# protoBoardHB.net
KiCad netlist of a schematic drawn in EAGLE
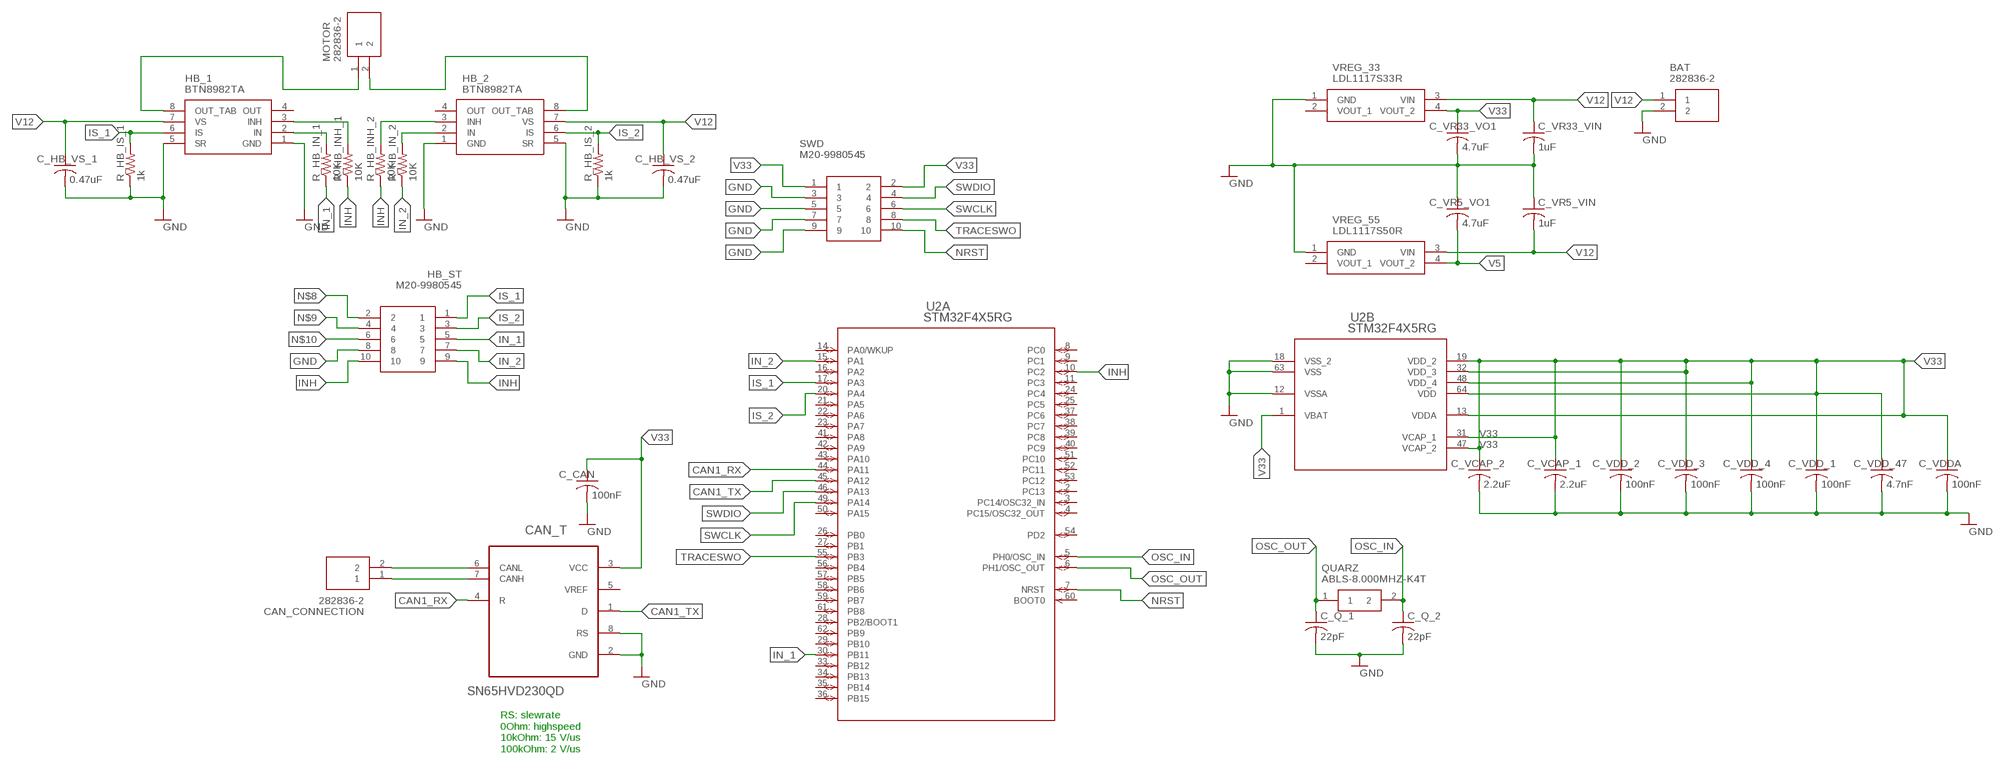
[diagram p0: schematic, sheet 1]

(export (version "E")
  (design (tool "Eeschema 10.0.6"))
  (components
    (comp (ref "BAT")
      (value "282836-2")
      (footprint "eagle-import:SHDR2W100P0X500_1X2_1000X820X1")
      (fields (field (name "MOUSER_PART_NUMBER") "571-2828362"))
      (libsource (lib "eagle-import") (part "282836-2"))
    )
    (comp (ref "CAN_CONNECTION")
      (value "282836-2")
      (footprint "eagle-import:SHDR2W100P0X500_1X2_1000X820X1")
      (fields (field (name "MOUSER_PART_NUMBER") "571-2828362"))
      (libsource (lib "eagle-import") (part "282836-2"))
    )
    (comp (ref "CAN_T")
      (value "SN65HVD230QD")
      (footprint "eagle-import:SOIC127P600X175-8N")
      (fields (field (name "MF") "TEXAS INSTRUMENTS") (field (name "MPN") "SN65HVD230QD.."))
      (libsource (lib "eagle-import") (part "SN65HVD230QD"))
    )
    (comp (ref "C_CAN")
      (value "100nF")
      (footprint "eagle-import:C1206")
      (libsource (lib "eagle-import") (part "C-USC1206"))
    )
    (comp (ref "C_HB_VS_1")
      (value "0.47uF")
      (footprint "eagle-import:C1206")
      (libsource (lib "eagle-import") (part "C-USC1206"))
    )
    (comp (ref "C_HB_VS_2")
      (value "0.47uF")
      (footprint "eagle-import:C1206")
      (libsource (lib "eagle-import") (part "C-USC1206"))
    )
    (comp (ref "C_Q_1")
      (value "22pF")
      (footprint "eagle-import:C0805")
      (libsource (lib "eagle-import") (part "C-USC0805"))
    )
    (comp (ref "C_Q_2")
      (value "22pF")
      (footprint "eagle-import:C0805")
      (libsource (lib "eagle-import") (part "C-USC0805"))
    )
    (comp (ref "C_VCAP_1")
      (value "2.2uF")
      (footprint "eagle-import:C1206")
      (libsource (lib "eagle-import") (part "C-USC1206"))
    )
    (comp (ref "C_VCAP_2")
      (value "2.2uF")
      (footprint "eagle-import:C1206")
      (libsource (lib "eagle-import") (part "C-USC1206"))
    )
    (comp (ref "C_VDDA")
      (value "100nF")
      (footprint "eagle-import:C1206")
      (libsource (lib "eagle-import") (part "C-USC1206"))
    )
    (comp (ref "C_VDD_1")
      (value "100nF")
      (footprint "eagle-import:C1206")
      (libsource (lib "eagle-import") (part "C-USC1206"))
    )
    (comp (ref "C_VDD_2")
      (value "100nF")
      (footprint "eagle-import:C1206")
      (libsource (lib "eagle-import") (part "C-USC1206"))
    )
    (comp (ref "C_VDD_3")
      (value "100nF")
      (footprint "eagle-import:C1206")
      (libsource (lib "eagle-import") (part "C-USC1206"))
    )
    (comp (ref "C_VDD_4")
      (value "100nF")
      (footprint "eagle-import:C1206")
      (libsource (lib "eagle-import") (part "C-USC1206"))
    )
    (comp (ref "C_VDD_47")
      (value "4.7nF")
      (footprint "eagle-import:C1206")
      (libsource (lib "eagle-import") (part "C-USC1206"))
    )
    (comp (ref "C_VR5_VIN")
      (value "1uF")
      (footprint "eagle-import:C1206")
      (libsource (lib "eagle-import") (part "C-USC1206"))
    )
    (comp (ref "C_VR5_VO1")
      (value "4.7uF")
      (footprint "eagle-import:C1206")
      (libsource (lib "eagle-import") (part "C-USC1206"))
    )
    (comp (ref "C_VR33_VIN")
      (value "1uF")
      (footprint "eagle-import:C1206")
      (libsource (lib "eagle-import") (part "C-USC1206"))
    )
    (comp (ref "C_VR33_VO1")
      (value "4.7uF")
      (footprint "eagle-import:C1206")
      (libsource (lib "eagle-import") (part "C-USC1206"))
    )
    (comp (ref "HB_1")
      (value "BTN8982TA")
      (footprint "eagle-import:TO127P1500X440-8N")
      (fields (field (name "MOUSER_PART_NUMBER") "726-BTN8982TA"))
      (libsource (lib "eagle-import") (part "BTN8982TA"))
    )
    (comp (ref "HB_2")
      (value "BTN8982TA")
      (footprint "eagle-import:TO127P1500X440-8N")
      (fields (field (name "MOUSER_PART_NUMBER") "726-BTN8982TA"))
      (libsource (lib "eagle-import") (part "BTN8982TA"))
    )
    (comp (ref "HB_ST")
      (value "M20-9980545")
      (footprint "eagle-import:HDRV10W80P254_2X5_1270X508X864")
      (fields (field (name "MOUSER_PART_NUMBER") "855-M20-9980545") (field (name "MF") "HARWIN"))
      (libsource (lib "eagle-import") (part "M20-9980545"))
    )
    (comp (ref "MOTOR")
      (value "282836-2")
      (footprint "eagle-import:SHDR2W100P0X500_1X2_1000X820X1")
      (fields (field (name "MOUSER_PART_NUMBER") "571-2828362"))
      (libsource (lib "eagle-import") (part "282836-2"))
    )
    (comp (ref "QUARZ")
      (value "ABLS-8.000MHZ-K4T")
      (footprint "eagle-import:ABLS-12.000MHZ-B2")
      (fields (field (name "MOUSER_PART_NUMBER") "815-ABLS-8.0MK4-T") (field (name "MF") "ABRACON"))
      (libsource (lib "eagle-import") (part "ABLS-8.000MHZ-K4T"))
    )
    (comp (ref "R_HB_INH_1")
      (value "10K")
      (footprint "eagle-import:R1206")
      (libsource (lib "eagle-import") (part "R-US_R1206"))
    )
    (comp (ref "R_HB_INH_2")
      (value "10K")
      (footprint "eagle-import:R1206")
      (libsource (lib "eagle-import") (part "R-US_R1206"))
    )
    (comp (ref "R_HB_IN_1")
      (value "10K")
      (footprint "eagle-import:R1206")
      (libsource (lib "eagle-import") (part "R-US_R1206"))
    )
    (comp (ref "R_HB_IN_2")
      (value "10K")
      (footprint "eagle-import:R1206")
      (libsource (lib "eagle-import") (part "R-US_R1206"))
    )
    (comp (ref "R_HB_IS_1")
      (value "1k")
      (footprint "eagle-import:R1206")
      (libsource (lib "eagle-import") (part "R-US_R1206"))
    )
    (comp (ref "R_HB_IS_2")
      (value "1k")
      (footprint "eagle-import:R1206")
      (libsource (lib "eagle-import") (part "R-US_R1206"))
    )
    (comp (ref "SWD")
      (value "M20-9980545")
      (footprint "eagle-import:HDRV10W80P254_2X5_1270X508X864")
      (fields (field (name "MOUSER_PART_NUMBER") "855-M20-9980545") (field (name "MF") "HARWIN"))
      (libsource (lib "eagle-import") (part "M20-9980545"))
    )
    (comp (ref "U2")
      (value "STM32F4X5RG")
      (footprint "eagle-import:LQFP64-10X10MM")
      (fields (field (name "OC_FARNELL") "unknown"))
      (libsource (lib "eagle-import") (part "STM32F4X5RG"))
    )
    (comp (ref "VREG_33")
      (value "LDL1117S33R")
      (footprint "eagle-import:SOT230P700X180-4N")
      (fields (field (name "MOUSER_PART_NUMBER") "511-LDL1117S33R") (field (name "MF") "STMICROELECTRONICS"))
      (libsource (lib "eagle-import") (part "LDL1117S33R"))
    )
    (comp (ref "VREG_55")
      (value "LDL1117S50R")
      (footprint "eagle-import:SOT230P700X180-4N")
      (fields (field (name "MOUSER_PART_NUMBER") "511-LDL1117S50R") (field (name "MF") "STMICROELECTRONICS"))
      (libsource (lib "eagle-import") (part "LDL1117S50R"))
    )
  )
  (nets
    (net (code "1") (name "CAN1_RX") (class "Default")
      (node (ref "CAN_T") (pin "4") (pinfunction "R_4") (pintype "output"))
      (node (ref "U2") (pin "44") (pinfunction "PA11_44") (pintype "bidirectional"))
    )
    (net (code "2") (name "CAN1_TX") (class "Default")
      (node (ref "CAN_T") (pin "1") (pinfunction "D_1") (pintype "input"))
      (node (ref "U2") (pin "45") (pinfunction "PA12_45") (pintype "bidirectional"))
    )
    (net (code "3") (name "GND") (class "Default")
      (node (ref "BAT") (pin "2") (pinfunction "2_2") (pintype "bidirectional"))
      (node (ref "CAN_T") (pin "2") (pinfunction "GND_2") (pintype "passive"))
      (node (ref "CAN_T") (pin "8") (pinfunction "RS_8") (pintype "input"))
      (node (ref "C_CAN") (pin "2") (pinfunction "2_2") (pintype "passive"))
      (node (ref "C_HB_VS_1") (pin "2") (pinfunction "2_2") (pintype "passive"))
      (node (ref "C_HB_VS_2") (pin "2") (pinfunction "2_2") (pintype "passive"))
      (node (ref "C_Q_1") (pin "2") (pinfunction "2_2") (pintype "passive"))
      (node (ref "C_Q_2") (pin "2") (pinfunction "2_2") (pintype "passive"))
      (node (ref "C_VCAP_1") (pin "2") (pinfunction "2_2") (pintype "passive"))
      (node (ref "C_VCAP_2") (pin "2") (pinfunction "2_2") (pintype "passive"))
      (node (ref "C_VDDA") (pin "2") (pinfunction "2_2") (pintype "passive"))
      (node (ref "C_VDD_1") (pin "2") (pinfunction "2_2") (pintype "passive"))
      (node (ref "C_VDD_2") (pin "2") (pinfunction "2_2") (pintype "passive"))
      (node (ref "C_VDD_3") (pin "2") (pinfunction "2_2") (pintype "passive"))
      (node (ref "C_VDD_4") (pin "2") (pinfunction "2_2") (pintype "passive"))
      (node (ref "C_VDD_47") (pin "2") (pinfunction "2_2") (pintype "passive"))
      (node (ref "C_VR33_VIN") (pin "2") (pinfunction "2_2") (pintype "passive"))
      (node (ref "C_VR33_VO1") (pin "2") (pinfunction "2_2") (pintype "passive"))
      (node (ref "C_VR5_VIN") (pin "1") (pinfunction "1_1") (pintype "passive"))
      (node (ref "C_VR5_VO1") (pin "1") (pinfunction "1_1") (pintype "passive"))
      (node (ref "HB_1") (pin "1") (pinfunction "GND_1") (pintype "power_in"))
      (node (ref "HB_1") (pin "5") (pinfunction "SR_5") (pintype "bidirectional"))
      (node (ref "HB_2") (pin "1") (pinfunction "GND_1") (pintype "power_in"))
      (node (ref "HB_2") (pin "5") (pinfunction "SR_5") (pintype "bidirectional"))
      (node (ref "HB_ST") (pin "8") (pinfunction "8_8") (pintype "bidirectional"))
      (node (ref "R_HB_IS_1") (pin "1") (pinfunction "1_1") (pintype "passive"))
      (node (ref "R_HB_IS_2") (pin "1") (pinfunction "1_1") (pintype "passive"))
      (node (ref "SWD") (pin "3") (pinfunction "3_3") (pintype "bidirectional"))
      (node (ref "SWD") (pin "5") (pinfunction "5_5") (pintype "bidirectional"))
      (node (ref "SWD") (pin "7") (pinfunction "7_7") (pintype "bidirectional"))
      (node (ref "SWD") (pin "9") (pinfunction "9_9") (pintype "bidirectional"))
      (node (ref "U2") (pin "12") (pinfunction "VSSA_12") (pintype "power_in"))
      (node (ref "U2") (pin "18") (pinfunction "VSS_2_18") (pintype "power_in"))
      (node (ref "U2") (pin "63") (pinfunction "VSS_63") (pintype "power_in"))
      (node (ref "VREG_33") (pin "1") (pinfunction "GND_1") (pintype "power_in"))
      (node (ref "VREG_55") (pin "1") (pinfunction "GND_1") (pintype "bidirectional"))
    )
    (net (code "4") (name "INH") (class "Default")
      (node (ref "HB_ST") (pin "10") (pinfunction "10_10") (pintype "bidirectional"))
      (node (ref "HB_ST") (pin "9") (pinfunction "9_9") (pintype "bidirectional"))
      (node (ref "R_HB_INH_1") (pin "1") (pinfunction "1_1") (pintype "passive"))
      (node (ref "R_HB_INH_2") (pin "1") (pinfunction "1_1") (pintype "passive"))
      (node (ref "U2") (pin "10") (pinfunction "PC2_10") (pintype "bidirectional"))
    )
    (net (code "5") (name "IN_1") (class "Default")
      (node (ref "HB_ST") (pin "5") (pinfunction "5_5") (pintype "bidirectional"))
      (node (ref "R_HB_IN_1") (pin "1") (pinfunction "1_1") (pintype "passive"))
      (node (ref "U2") (pin "30") (pinfunction "PB11_30") (pintype "bidirectional"))
    )
    (net (code "6") (name "IN_2") (class "Default")
      (node (ref "HB_ST") (pin "7") (pinfunction "7_7") (pintype "bidirectional"))
      (node (ref "R_HB_IN_2") (pin "1") (pinfunction "1_1") (pintype "passive"))
      (node (ref "U2") (pin "15") (pinfunction "PA1_15") (pintype "bidirectional"))
    )
    (net (code "7") (name "IS_1") (class "Default")
      (node (ref "HB_1") (pin "6") (pinfunction "IS_6") (pintype "bidirectional"))
      (node (ref "HB_ST") (pin "1") (pinfunction "1_1") (pintype "bidirectional"))
      (node (ref "R_HB_IS_1") (pin "2") (pinfunction "2_2") (pintype "passive"))
      (node (ref "U2") (pin "17") (pinfunction "PA3_17") (pintype "bidirectional"))
    )
    (net (code "8") (name "IS_2") (class "Default")
      (node (ref "HB_2") (pin "6") (pinfunction "IS_6") (pintype "bidirectional"))
      (node (ref "HB_ST") (pin "3") (pinfunction "3_3") (pintype "bidirectional"))
      (node (ref "R_HB_IS_2") (pin "2") (pinfunction "2_2") (pintype "passive"))
      (node (ref "U2") (pin "20") (pinfunction "PA4_20") (pintype "bidirectional"))
    )
    (net (code "9") (name "N$8") (class "Default")
      (node (ref "HB_ST") (pin "2") (pinfunction "2_2") (pintype "bidirectional"))
    )
    (net (code "10") (name "N$9") (class "Default")
      (node (ref "HB_ST") (pin "4") (pinfunction "4_4") (pintype "bidirectional"))
    )
    (net (code "11") (name "N$10") (class "Default")
      (node (ref "HB_ST") (pin "6") (pinfunction "6_6") (pintype "bidirectional"))
    )
    (net (code "12") (name "NRST") (class "Default")
      (node (ref "SWD") (pin "10") (pinfunction "10_10") (pintype "bidirectional"))
      (node (ref "U2") (pin "7") (pinfunction "NRST_7") (pintype "bidirectional"))
    )
    (net (code "13") (name "Net-(CAN_T-CANH)") (class "Default")
      (node (ref "CAN_CONNECTION") (pin "1") (pinfunction "1_1") (pintype "bidirectional"))
      (node (ref "CAN_T") (pin "7") (pinfunction "CANH_7") (pintype "output"))
    )
    (net (code "14") (name "Net-(CAN_T-CANL)") (class "Default")
      (node (ref "CAN_CONNECTION") (pin "2") (pinfunction "2_2") (pintype "bidirectional"))
      (node (ref "CAN_T") (pin "6") (pinfunction "CANL_6") (pintype "output"))
    )
    (net (code "15") (name "Net-(HB_1-IN)") (class "Default")
      (node (ref "HB_1") (pin "2") (pinfunction "IN_2") (pintype "input"))
      (node (ref "R_HB_IN_1") (pin "2") (pinfunction "2_2") (pintype "passive"))
    )
    (net (code "16") (name "Net-(HB_1-INH)") (class "Default")
      (node (ref "HB_1") (pin "3") (pinfunction "INH_3") (pintype "input"))
      (node (ref "R_HB_INH_1") (pin "2") (pinfunction "2_2") (pintype "passive"))
    )
    (net (code "17") (name "Net-(HB_1-OUT_TAB)") (class "Default")
      (node (ref "HB_1") (pin "8") (pinfunction "OUT_TAB_8") (pintype "output"))
      (node (ref "MOTOR") (pin "1") (pinfunction "1_1") (pintype "bidirectional"))
    )
    (net (code "18") (name "Net-(HB_2-IN)") (class "Default")
      (node (ref "HB_2") (pin "2") (pinfunction "IN_2") (pintype "input"))
      (node (ref "R_HB_IN_2") (pin "2") (pinfunction "2_2") (pintype "passive"))
    )
    (net (code "19") (name "Net-(HB_2-INH)") (class "Default")
      (node (ref "HB_2") (pin "3") (pinfunction "INH_3") (pintype "input"))
      (node (ref "R_HB_INH_2") (pin "2") (pinfunction "2_2") (pintype "passive"))
    )
    (net (code "20") (name "Net-(HB_2-OUT_TAB)") (class "Default")
      (node (ref "HB_2") (pin "8") (pinfunction "OUT_TAB_8") (pintype "output"))
      (node (ref "MOTOR") (pin "2") (pinfunction "2_2") (pintype "bidirectional"))
    )
    (net (code "21") (name "OSC_IN") (class "Default")
      (node (ref "C_Q_2") (pin "1") (pinfunction "1_1") (pintype "passive"))
      (node (ref "QUARZ") (pin "2") (pinfunction "2_2") (pintype "bidirectional"))
      (node (ref "U2") (pin "5") (pinfunction "PH0/OSC_IN_5") (pintype "bidirectional"))
    )
    (net (code "22") (name "OSC_OUT") (class "Default")
      (node (ref "C_Q_1") (pin "1") (pinfunction "1_1") (pintype "passive"))
      (node (ref "QUARZ") (pin "1") (pinfunction "1_1") (pintype "bidirectional"))
      (node (ref "U2") (pin "6") (pinfunction "PH1/OSC_OUT_6") (pintype "bidirectional"))
    )
    (net (code "23") (name "SWCLK") (class "Default")
      (node (ref "SWD") (pin "6") (pinfunction "6_6") (pintype "bidirectional"))
      (node (ref "U2") (pin "49") (pinfunction "PA14_49") (pintype "bidirectional"))
    )
    (net (code "24") (name "SWDIO") (class "Default")
      (node (ref "SWD") (pin "4") (pinfunction "4_4") (pintype "bidirectional"))
      (node (ref "U2") (pin "46") (pinfunction "PA13_46") (pintype "bidirectional"))
    )
    (net (code "25") (name "TRACESWO") (class "Default")
      (node (ref "SWD") (pin "8") (pinfunction "8_8") (pintype "bidirectional"))
      (node (ref "U2") (pin "55") (pinfunction "PB3_55") (pintype "bidirectional"))
    )
    (net (code "26") (name "V5") (class "Default")
      (node (ref "C_VR5_VO1") (pin "2") (pinfunction "2_2") (pintype "passive"))
      (node (ref "VREG_55") (pin "4") (pinfunction "VOUT_2_4") (pintype "bidirectional"))
    )
    (net (code "27") (name "V12") (class "Default")
      (node (ref "BAT") (pin "1") (pinfunction "1_1") (pintype "bidirectional"))
      (node (ref "C_HB_VS_1") (pin "1") (pinfunction "1_1") (pintype "passive"))
      (node (ref "C_HB_VS_2") (pin "1") (pinfunction "1_1") (pintype "passive"))
      (node (ref "C_VR33_VIN") (pin "1") (pinfunction "1_1") (pintype "passive"))
      (node (ref "C_VR5_VIN") (pin "2") (pinfunction "2_2") (pintype "passive"))
      (node (ref "HB_1") (pin "7") (pinfunction "VS_7") (pintype "bidirectional"))
      (node (ref "HB_2") (pin "7") (pinfunction "VS_7") (pintype "bidirectional"))
      (node (ref "VREG_33") (pin "3") (pinfunction "VIN_3") (pintype "input"))
      (node (ref "VREG_55") (pin "3") (pinfunction "VIN_3") (pintype "bidirectional"))
    )
    (net (code "28") (name "V33") (class "Default")
      (node (ref "CAN_T") (pin "3") (pinfunction "VCC_3") (pintype "power_in"))
      (node (ref "C_CAN") (pin "1") (pinfunction "1_1") (pintype "passive"))
      (node (ref "C_VCAP_1") (pin "1") (pinfunction "1_1") (pintype "passive"))
      (node (ref "C_VCAP_2") (pin "1") (pinfunction "1_1") (pintype "passive"))
      (node (ref "C_VDDA") (pin "1") (pinfunction "1_1") (pintype "passive"))
      (node (ref "C_VDD_1") (pin "1") (pinfunction "1_1") (pintype "passive"))
      (node (ref "C_VDD_2") (pin "1") (pinfunction "1_1") (pintype "passive"))
      (node (ref "C_VDD_3") (pin "1") (pinfunction "1_1") (pintype "passive"))
      (node (ref "C_VDD_4") (pin "1") (pinfunction "1_1") (pintype "passive"))
      (node (ref "C_VDD_47") (pin "1") (pinfunction "1_1") (pintype "passive"))
      (node (ref "C_VR33_VO1") (pin "1") (pinfunction "1_1") (pintype "passive"))
      (node (ref "SWD") (pin "1") (pinfunction "1_1") (pintype "bidirectional"))
      (node (ref "SWD") (pin "2") (pinfunction "2_2") (pintype "bidirectional"))
      (node (ref "U2") (pin "1") (pinfunction "VBAT_1") (pintype "power_in"))
      (node (ref "U2") (pin "13") (pinfunction "VDDA_13") (pintype "power_in"))
      (node (ref "U2") (pin "19") (pinfunction "VDD_2_19") (pintype "power_in"))
      (node (ref "U2") (pin "31") (pinfunction "VCAP_1_31") (pintype "power_in"))
      (node (ref "U2") (pin "32") (pinfunction "VDD_3_32") (pintype "power_in"))
      (node (ref "U2") (pin "47") (pinfunction "VCAP_2_47") (pintype "power_in"))
      (node (ref "U2") (pin "48") (pinfunction "VDD_4_48") (pintype "power_in"))
      (node (ref "U2") (pin "64") (pinfunction "VDD_64") (pintype "power_in"))
      (node (ref "VREG_33") (pin "4") (pinfunction "VOUT_2_4") (pintype "output"))
    )
    (net (code "29") (name "unconnected-(CAN_T-VREF-Pad5)") (class "Default")
      (node (ref "CAN_T") (pin "5") (pinfunction "VREF_5") (pintype "input"))
    )
    (net (code "30") (name "unconnected-(HB_1-OUT-Pad4)") (class "Default")
      (node (ref "HB_1") (pin "4") (pinfunction "OUT_4") (pintype "output"))
    )
    (net (code "31") (name "unconnected-(HB_2-OUT-Pad4)") (class "Default")
      (node (ref "HB_2") (pin "4") (pinfunction "OUT_4") (pintype "output"))
    )
    (net (code "32") (name "unconnected-(U2A-BOOT0-Pad60)") (class "Default")
      (node (ref "U2") (pin "60") (pinfunction "BOOT0_60") (pintype "input"))
    )
    (net (code "33") (name "unconnected-(U2A-PA0{slash}WKUP-Pad14)") (class "Default")
      (node (ref "U2") (pin "14") (pinfunction "PA0/WKUP_14") (pintype "bidirectional"))
    )
    (net (code "34") (name "unconnected-(U2A-PA2-Pad16)") (class "Default")
      (node (ref "U2") (pin "16") (pinfunction "PA2_16") (pintype "bidirectional"))
    )
    (net (code "35") (name "unconnected-(U2A-PA5-Pad21)") (class "Default")
      (node (ref "U2") (pin "21") (pinfunction "PA5_21") (pintype "bidirectional"))
    )
    (net (code "36") (name "unconnected-(U2A-PA6-Pad22)") (class "Default")
      (node (ref "U2") (pin "22") (pinfunction "PA6_22") (pintype "bidirectional"))
    )
    (net (code "37") (name "unconnected-(U2A-PA7-Pad23)") (class "Default")
      (node (ref "U2") (pin "23") (pinfunction "PA7_23") (pintype "bidirectional"))
    )
    (net (code "38") (name "unconnected-(U2A-PA8-Pad41)") (class "Default")
      (node (ref "U2") (pin "41") (pinfunction "PA8_41") (pintype "bidirectional"))
    )
    (net (code "39") (name "unconnected-(U2A-PA9-Pad42)") (class "Default")
      (node (ref "U2") (pin "42") (pinfunction "PA9_42") (pintype "bidirectional"))
    )
    (net (code "40") (name "unconnected-(U2A-PA10-Pad43)") (class "Default")
      (node (ref "U2") (pin "43") (pinfunction "PA10_43") (pintype "bidirectional"))
    )
    (net (code "41") (name "unconnected-(U2A-PA15-Pad50)") (class "Default")
      (node (ref "U2") (pin "50") (pinfunction "PA15_50") (pintype "bidirectional"))
    )
    (net (code "42") (name "unconnected-(U2A-PB0-Pad26)") (class "Default")
      (node (ref "U2") (pin "26") (pinfunction "PB0_26") (pintype "bidirectional"))
    )
    (net (code "43") (name "unconnected-(U2A-PB1-Pad27)") (class "Default")
      (node (ref "U2") (pin "27") (pinfunction "PB1_27") (pintype "bidirectional"))
    )
    (net (code "44") (name "unconnected-(U2A-PB2{slash}BOOT1-Pad28)") (class "Default")
      (node (ref "U2") (pin "28") (pinfunction "PB2/BOOT1_28") (pintype "bidirectional"))
    )
    (net (code "45") (name "unconnected-(U2A-PB4-Pad56)") (class "Default")
      (node (ref "U2") (pin "56") (pinfunction "PB4_56") (pintype "bidirectional"))
    )
    (net (code "46") (name "unconnected-(U2A-PB5-Pad57)") (class "Default")
      (node (ref "U2") (pin "57") (pinfunction "PB5_57") (pintype "bidirectional"))
    )
    (net (code "47") (name "unconnected-(U2A-PB6-Pad58)") (class "Default")
      (node (ref "U2") (pin "58") (pinfunction "PB6_58") (pintype "bidirectional"))
    )
    (net (code "48") (name "unconnected-(U2A-PB7-Pad59)") (class "Default")
      (node (ref "U2") (pin "59") (pinfunction "PB7_59") (pintype "bidirectional"))
    )
    (net (code "49") (name "unconnected-(U2A-PB8-Pad61)") (class "Default")
      (node (ref "U2") (pin "61") (pinfunction "PB8_61") (pintype "bidirectional"))
    )
    (net (code "50") (name "unconnected-(U2A-PB9-Pad62)") (class "Default")
      (node (ref "U2") (pin "62") (pinfunction "PB9_62") (pintype "bidirectional"))
    )
    (net (code "51") (name "unconnected-(U2A-PB10-Pad29)") (class "Default")
      (node (ref "U2") (pin "29") (pinfunction "PB10_29") (pintype "bidirectional"))
    )
    (net (code "52") (name "unconnected-(U2A-PB12-Pad33)") (class "Default")
      (node (ref "U2") (pin "33") (pinfunction "PB12_33") (pintype "bidirectional"))
    )
    (net (code "53") (name "unconnected-(U2A-PB13-Pad34)") (class "Default")
      (node (ref "U2") (pin "34") (pinfunction "PB13_34") (pintype "bidirectional"))
    )
    (net (code "54") (name "unconnected-(U2A-PB14-Pad35)") (class "Default")
      (node (ref "U2") (pin "35") (pinfunction "PB14_35") (pintype "bidirectional"))
    )
    (net (code "55") (name "unconnected-(U2A-PB15-Pad36)") (class "Default")
      (node (ref "U2") (pin "36") (pinfunction "PB15_36") (pintype "bidirectional"))
    )
    (net (code "56") (name "unconnected-(U2A-PC0-Pad8)") (class "Default")
      (node (ref "U2") (pin "8") (pinfunction "PC0_8") (pintype "bidirectional"))
    )
    (net (code "57") (name "unconnected-(U2A-PC1-Pad9)") (class "Default")
      (node (ref "U2") (pin "9") (pinfunction "PC1_9") (pintype "bidirectional"))
    )
    (net (code "58") (name "unconnected-(U2A-PC3-Pad11)") (class "Default")
      (node (ref "U2") (pin "11") (pinfunction "PC3_11") (pintype "bidirectional"))
    )
    (net (code "59") (name "unconnected-(U2A-PC4-Pad24)") (class "Default")
      (node (ref "U2") (pin "24") (pinfunction "PC4_24") (pintype "bidirectional"))
    )
    (net (code "60") (name "unconnected-(U2A-PC5-Pad25)") (class "Default")
      (node (ref "U2") (pin "25") (pinfunction "PC5_25") (pintype "bidirectional"))
    )
    (net (code "61") (name "unconnected-(U2A-PC6-Pad37)") (class "Default")
      (node (ref "U2") (pin "37") (pinfunction "PC6_37") (pintype "bidirectional"))
    )
    (net (code "62") (name "unconnected-(U2A-PC7-Pad38)") (class "Default")
      (node (ref "U2") (pin "38") (pinfunction "PC7_38") (pintype "bidirectional"))
    )
    (net (code "63") (name "unconnected-(U2A-PC8-Pad39)") (class "Default")
      (node (ref "U2") (pin "39") (pinfunction "PC8_39") (pintype "bidirectional"))
    )
    (net (code "64") (name "unconnected-(U2A-PC9-Pad40)") (class "Default")
      (node (ref "U2") (pin "40") (pinfunction "PC9_40") (pintype "bidirectional"))
    )
    (net (code "65") (name "unconnected-(U2A-PC10-Pad51)") (class "Default")
      (node (ref "U2") (pin "51") (pinfunction "PC10_51") (pintype "bidirectional"))
    )
    (net (code "66") (name "unconnected-(U2A-PC11-Pad52)") (class "Default")
      (node (ref "U2") (pin "52") (pinfunction "PC11_52") (pintype "bidirectional"))
    )
    (net (code "67") (name "unconnected-(U2A-PC12-Pad53)") (class "Default")
      (node (ref "U2") (pin "53") (pinfunction "PC12_53") (pintype "bidirectional"))
    )
    (net (code "68") (name "unconnected-(U2A-PC13-Pad2)") (class "Default")
      (node (ref "U2") (pin "2") (pinfunction "PC13_2") (pintype "bidirectional"))
    )
    (net (code "69") (name "unconnected-(U2A-PC14{slash}OSC32_IN-Pad3)") (class "Default")
      (node (ref "U2") (pin "3") (pinfunction "PC14/OSC32_IN_3") (pintype "bidirectional"))
    )
    (net (code "70") (name "unconnected-(U2A-PC15{slash}OSC32_OUT-Pad4)") (class "Default")
      (node (ref "U2") (pin "4") (pinfunction "PC15/OSC32_OUT_4") (pintype "bidirectional"))
    )
    (net (code "71") (name "unconnected-(U2A-PD2-Pad54)") (class "Default")
      (node (ref "U2") (pin "54") (pinfunction "PD2_54") (pintype "bidirectional"))
    )
    (net (code "72") (name "unconnected-(VREG_33-VOUT_1-Pad2)") (class "Default")
      (node (ref "VREG_33") (pin "2") (pinfunction "VOUT_1_2") (pintype "output"))
    )
    (net (code "73") (name "unconnected-(VREG_55-VOUT_1-Pad2)") (class "Default")
      (node (ref "VREG_55") (pin "2") (pinfunction "VOUT_1_2") (pintype "bidirectional"))
    )
  )
)
